# Sheet8.net
KiCad netlist of a schematic drawn in Altium Designer
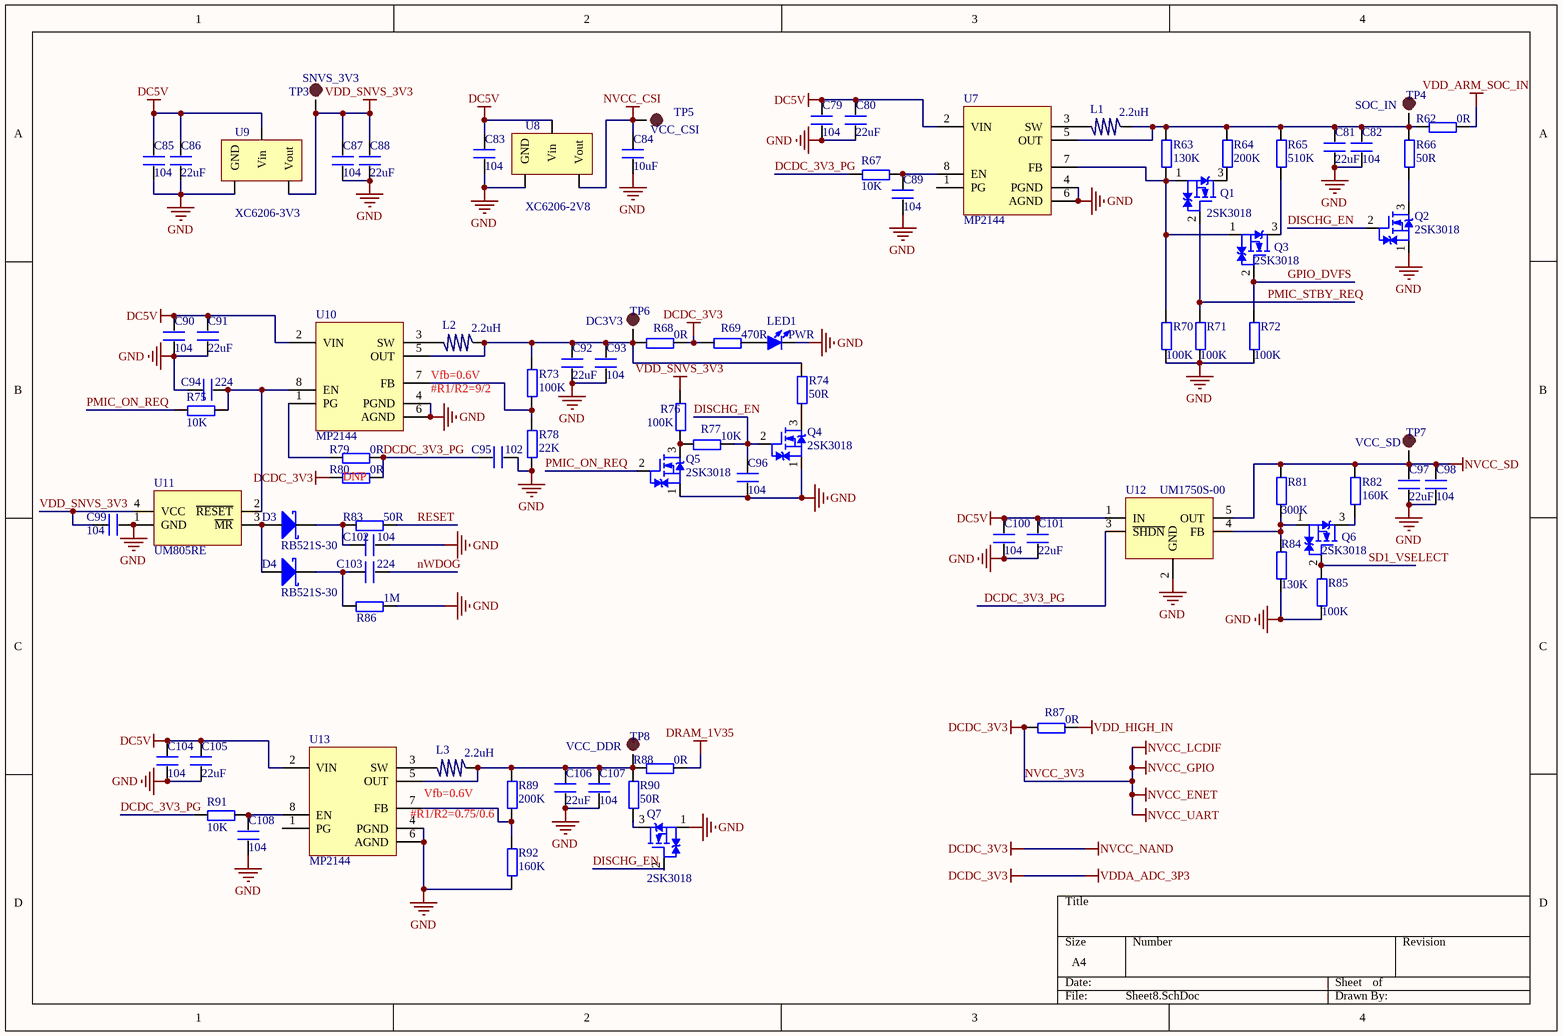
[diagram p0: Sheet8.SchDoc]

(export (version "E")
  (design (tool "Eeschema 10.0.6"))
  (components
    (comp (ref "C79")
      (value "104")
      (footprint "C 0402")
      (libsource (lib "IMX6ULL_CORE(核心板)_V1.4") (part "C"))
    )
    (comp (ref "C80")
      (value "22uF")
      (footprint "C 0402")
      (libsource (lib "IMX6ULL_CORE(核心板)_V1.4") (part "C"))
    )
    (comp (ref "C81")
      (value "22uF")
      (footprint "C 0402")
      (libsource (lib "IMX6ULL_CORE(核心板)_V1.4") (part "C"))
    )
    (comp (ref "C82")
      (value "104")
      (footprint "C 0402")
      (libsource (lib "IMX6ULL_CORE(核心板)_V1.4") (part "C"))
    )
    (comp (ref "C83")
      (value "104")
      (footprint "C 0402")
      (libsource (lib "IMX6ULL_CORE(核心板)_V1.4") (part "C"))
    )
    (comp (ref "C84")
      (value "10uF")
      (footprint "C 0402")
      (libsource (lib "IMX6ULL_CORE(核心板)_V1.4") (part "C"))
    )
    (comp (ref "C85")
      (value "104")
      (footprint "C 0402")
      (libsource (lib "IMX6ULL_CORE(核心板)_V1.4") (part "C"))
    )
    (comp (ref "C86")
      (value "22uF")
      (footprint "C 0402")
      (libsource (lib "IMX6ULL_CORE(核心板)_V1.4") (part "C"))
    )
    (comp (ref "C87")
      (value "104")
      (footprint "C 0402")
      (libsource (lib "IMX6ULL_CORE(核心板)_V1.4") (part "C"))
    )
    (comp (ref "C88")
      (value "22uF")
      (footprint "C 0402")
      (libsource (lib "IMX6ULL_CORE(核心板)_V1.4") (part "C"))
    )
    (comp (ref "C89")
      (value "104")
      (footprint "C 0402")
      (libsource (lib "IMX6ULL_CORE(核心板)_V1.4") (part "C"))
    )
    (comp (ref "C90")
      (value "104")
      (footprint "C 0402")
      (libsource (lib "IMX6ULL_CORE(核心板)_V1.4") (part "C"))
    )
    (comp (ref "C91")
      (value "22uF")
      (footprint "C 0402")
      (libsource (lib "IMX6ULL_CORE(核心板)_V1.4") (part "C"))
    )
    (comp (ref "C92")
      (value "22uF")
      (footprint "C 0402")
      (libsource (lib "IMX6ULL_CORE(核心板)_V1.4") (part "C"))
    )
    (comp (ref "C93")
      (value "104")
      (footprint "C 0402")
      (libsource (lib "IMX6ULL_CORE(核心板)_V1.4") (part "C"))
    )
    (comp (ref "C94")
      (value "224")
      (footprint "C 0402")
      (libsource (lib "IMX6ULL_CORE(核心板)_V1.4") (part "C"))
    )
    (comp (ref "C95")
      (value "102")
      (footprint "C 0402")
      (libsource (lib "IMX6ULL_CORE(核心板)_V1.4") (part "C"))
    )
    (comp (ref "C96")
      (value "104")
      (footprint "C 0402")
      (libsource (lib "IMX6ULL_CORE(核心板)_V1.4") (part "C"))
    )
    (comp (ref "C97")
      (value "22uF")
      (footprint "C 0402")
      (libsource (lib "IMX6ULL_CORE(核心板)_V1.4") (part "C"))
    )
    (comp (ref "C98")
      (value "104")
      (footprint "C 0402")
      (libsource (lib "IMX6ULL_CORE(核心板)_V1.4") (part "C"))
    )
    (comp (ref "C99")
      (value "104")
      (footprint "C 0402")
      (libsource (lib "IMX6ULL_CORE(核心板)_V1.4") (part "C"))
    )
    (comp (ref "C100")
      (value "104")
      (footprint "C 0402")
      (libsource (lib "IMX6ULL_CORE(核心板)_V1.4") (part "C"))
    )
    (comp (ref "C101")
      (value "22uF")
      (footprint "C 0402")
      (libsource (lib "IMX6ULL_CORE(核心板)_V1.4") (part "C"))
    )
    (comp (ref "C102")
      (value "104")
      (footprint "C 0402")
      (libsource (lib "IMX6ULL_CORE(核心板)_V1.4") (part "C"))
    )
    (comp (ref "C103")
      (value "224")
      (footprint "C 0402")
      (libsource (lib "IMX6ULL_CORE(核心板)_V1.4") (part "C"))
    )
    (comp (ref "C104")
      (value "104")
      (footprint "C 0402")
      (libsource (lib "IMX6ULL_CORE(核心板)_V1.4") (part "C"))
    )
    (comp (ref "C105")
      (value "22uF")
      (footprint "C 0402")
      (libsource (lib "IMX6ULL_CORE(核心板)_V1.4") (part "C"))
    )
    (comp (ref "C106")
      (value "22uF")
      (footprint "C 0402")
      (libsource (lib "IMX6ULL_CORE(核心板)_V1.4") (part "C"))
    )
    (comp (ref "C107")
      (value "104")
      (footprint "C 0402")
      (libsource (lib "IMX6ULL_CORE(核心板)_V1.4") (part "C"))
    )
    (comp (ref "C108")
      (value "104")
      (footprint "C 0402")
      (libsource (lib "IMX6ULL_CORE(核心板)_V1.4") (part "C"))
    )
    (comp (ref "D3")
      (value "RB521S-30")
      (footprint "SOD-523")
      (libsource (lib "IMX6ULL_CORE(核心板)_V1.4") (part "RB521S-30"))
    )
    (comp (ref "D4")
      (value "RB521S-30")
      (footprint "SOD-523")
      (libsource (lib "IMX6ULL_CORE(核心板)_V1.4") (part "RB521S-30"))
    )
    (comp (ref "L1")
      (value "2.2uH")
      (footprint "NR3015")
      (libsource (lib "IMX6ULL_CORE(核心板)_V1.4") (part "L"))
    )
    (comp (ref "L2")
      (value "2.2uH")
      (footprint "NR3015")
      (libsource (lib "IMX6ULL_CORE(核心板)_V1.4") (part "L"))
    )
    (comp (ref "L3")
      (value "2.2uH")
      (footprint "NR3015")
      (libsource (lib "IMX6ULL_CORE(核心板)_V1.4") (part "L"))
    )
    (comp (ref "LED1")
      (value "PWR")
      (footprint "LED 0603B")
      (description "贴片LED")
      (fields (field (name "版权归属") "源创客"))
      (libsource (lib "IMX6ULL_CORE(核心板)_V1.4") (part "LED-SMD"))
    )
    (comp (ref "Q1")
      (value "2SK3018")
      (footprint "SC70-3L")
      (description "N沟场效应管  30V,0.1A")
      (fields (field (name "版权归属") "源创客"))
      (libsource (lib "IMX6ULL_CORE(核心板)_V1.4") (part "2SK3018"))
    )
    (comp (ref "Q2")
      (value "2SK3018")
      (footprint "SC70-3L")
      (description "N沟场效应管  30V,0.1A")
      (fields (field (name "版权归属") "源创客"))
      (libsource (lib "IMX6ULL_CORE(核心板)_V1.4") (part "2SK3018"))
    )
    (comp (ref "Q3")
      (value "2SK3018")
      (footprint "SC70-3L")
      (description "N沟场效应管  30V,0.1A")
      (fields (field (name "版权归属") "源创客"))
      (libsource (lib "IMX6ULL_CORE(核心板)_V1.4") (part "2SK3018"))
    )
    (comp (ref "Q4")
      (value "2SK3018")
      (footprint "SC70-3L")
      (description "N沟场效应管  30V,0.1A")
      (fields (field (name "版权归属") "源创客"))
      (libsource (lib "IMX6ULL_CORE(核心板)_V1.4") (part "2SK3018"))
    )
    (comp (ref "Q5")
      (value "2SK3018")
      (footprint "SC70-3L")
      (description "N沟场效应管  30V,0.1A")
      (fields (field (name "版权归属") "源创客"))
      (libsource (lib "IMX6ULL_CORE(核心板)_V1.4") (part "2SK3018"))
    )
    (comp (ref "Q6")
      (value "2SK3018")
      (footprint "SC70-3L")
      (description "N沟场效应管  30V,0.1A")
      (fields (field (name "版权归属") "源创客"))
      (libsource (lib "IMX6ULL_CORE(核心板)_V1.4") (part "2SK3018"))
    )
    (comp (ref "Q7")
      (value "2SK3018")
      (footprint "SC70-3L")
      (description "N沟场效应管  30V,0.1A")
      (fields (field (name "版权归属") "源创客"))
      (libsource (lib "IMX6ULL_CORE(核心板)_V1.4") (part "2SK3018"))
    )
    (comp (ref "R62") (value "0R") (footprint "R 0402") (libsource (lib "IMX6ULL_CORE(核心板)_V1.4") (part "R")))
    (comp (ref "R63")
      (value "130K")
      (footprint "R 0402")
      (libsource (lib "IMX6ULL_CORE(核心板)_V1.4") (part "R"))
    )
    (comp (ref "R64")
      (value "200K")
      (footprint "R 0402")
      (libsource (lib "IMX6ULL_CORE(核心板)_V1.4") (part "R"))
    )
    (comp (ref "R65")
      (value "510K")
      (footprint "R 0402")
      (libsource (lib "IMX6ULL_CORE(核心板)_V1.4") (part "R"))
    )
    (comp (ref "R66")
      (value "50R")
      (footprint "R 0402")
      (libsource (lib "IMX6ULL_CORE(核心板)_V1.4") (part "R"))
    )
    (comp (ref "R67")
      (value "10K")
      (footprint "R 0402")
      (libsource (lib "IMX6ULL_CORE(核心板)_V1.4") (part "R"))
    )
    (comp (ref "R68") (value "0R") (footprint "R 0402") (libsource (lib "IMX6ULL_CORE(核心板)_V1.4") (part "R")))
    (comp (ref "R69")
      (value "470R")
      (footprint "R 0402")
      (libsource (lib "IMX6ULL_CORE(核心板)_V1.4") (part "R"))
    )
    (comp (ref "R70")
      (value "100K")
      (footprint "R 0402")
      (libsource (lib "IMX6ULL_CORE(核心板)_V1.4") (part "R"))
    )
    (comp (ref "R71")
      (value "100K")
      (footprint "R 0402")
      (libsource (lib "IMX6ULL_CORE(核心板)_V1.4") (part "R"))
    )
    (comp (ref "R72")
      (value "100K")
      (footprint "R 0402")
      (libsource (lib "IMX6ULL_CORE(核心板)_V1.4") (part "R"))
    )
    (comp (ref "R73")
      (value "100K")
      (footprint "R 0402")
      (libsource (lib "IMX6ULL_CORE(核心板)_V1.4") (part "R"))
    )
    (comp (ref "R74")
      (value "50R")
      (footprint "R 0402")
      (libsource (lib "IMX6ULL_CORE(核心板)_V1.4") (part "R"))
    )
    (comp (ref "R75")
      (value "10K")
      (footprint "R 0402")
      (libsource (lib "IMX6ULL_CORE(核心板)_V1.4") (part "R"))
    )
    (comp (ref "R76")
      (value "100K")
      (footprint "R 0402")
      (libsource (lib "IMX6ULL_CORE(核心板)_V1.4") (part "R"))
    )
    (comp (ref "R77")
      (value "10K")
      (footprint "R 0402")
      (libsource (lib "IMX6ULL_CORE(核心板)_V1.4") (part "R"))
    )
    (comp (ref "R78")
      (value "22K")
      (footprint "R 0402")
      (libsource (lib "IMX6ULL_CORE(核心板)_V1.4") (part "R"))
    )
    (comp (ref "R79") (value "0R") (footprint "R 0402") (libsource (lib "IMX6ULL_CORE(核心板)_V1.4") (part "R")))
    (comp (ref "R80") (value "0R") (footprint "R 0402") (libsource (lib "IMX6ULL_CORE(核心板)_V1.4") (part "R")))
    (comp (ref "R81")
      (value "300K")
      (footprint "R 0402")
      (libsource (lib "IMX6ULL_CORE(核心板)_V1.4") (part "R"))
    )
    (comp (ref "R82")
      (value "160K")
      (footprint "R 0402")
      (libsource (lib "IMX6ULL_CORE(核心板)_V1.4") (part "R"))
    )
    (comp (ref "R83")
      (value "50R")
      (footprint "R 0402")
      (libsource (lib "IMX6ULL_CORE(核心板)_V1.4") (part "R"))
    )
    (comp (ref "R84")
      (value "130K")
      (footprint "R 0402")
      (libsource (lib "IMX6ULL_CORE(核心板)_V1.4") (part "R"))
    )
    (comp (ref "R85")
      (value "100K")
      (footprint "R 0402")
      (libsource (lib "IMX6ULL_CORE(核心板)_V1.4") (part "R"))
    )
    (comp (ref "R86") (value "1M") (footprint "R 0402") (libsource (lib "IMX6ULL_CORE(核心板)_V1.4") (part "R")))
    (comp (ref "R87") (value "0R") (footprint "R 0402") (libsource (lib "IMX6ULL_CORE(核心板)_V1.4") (part "R")))
    (comp (ref "R88") (value "0R") (footprint "R 0402") (libsource (lib "IMX6ULL_CORE(核心板)_V1.4") (part "R")))
    (comp (ref "R89")
      (value "200K")
      (footprint "R 0402")
      (libsource (lib "IMX6ULL_CORE(核心板)_V1.4") (part "R"))
    )
    (comp (ref "R90")
      (value "50R")
      (footprint "R 0402")
      (libsource (lib "IMX6ULL_CORE(核心板)_V1.4") (part "R"))
    )
    (comp (ref "R91")
      (value "10K")
      (footprint "R 0402")
      (libsource (lib "IMX6ULL_CORE(核心板)_V1.4") (part "R"))
    )
    (comp (ref "R92")
      (value "160K")
      (footprint "R 0402")
      (libsource (lib "IMX6ULL_CORE(核心板)_V1.4") (part "R"))
    )
    (comp (ref "TP3")
      (value "SNVS_3V3")
      (footprint "TP-1.0")
      (description "测试点")
      (libsource (lib "IMX6ULL_CORE(核心板)_V1.4") (part "TEST-POINT"))
    )
    (comp (ref "TP4")
      (value "SOC_IN")
      (footprint "TP-1.0")
      (description "测试点")
      (libsource (lib "IMX6ULL_CORE(核心板)_V1.4") (part "TEST-POINT"))
    )
    (comp (ref "TP5")
      (value "VCC_CSI")
      (footprint "TP-1.0")
      (description "测试点")
      (libsource (lib "IMX6ULL_CORE(核心板)_V1.4") (part "TEST-POINT"))
    )
    (comp (ref "TP6")
      (value "DC3V3")
      (footprint "TP-1.0")
      (description "测试点")
      (libsource (lib "IMX6ULL_CORE(核心板)_V1.4") (part "TEST-POINT"))
    )
    (comp (ref "TP7")
      (value "VCC_SD")
      (footprint "TP-1.0")
      (description "测试点")
      (libsource (lib "IMX6ULL_CORE(核心板)_V1.4") (part "TEST-POINT"))
    )
    (comp (ref "TP8")
      (value "VCC_DDR")
      (footprint "TP-1.0")
      (description "测试点")
      (libsource (lib "IMX6ULL_CORE(核心板)_V1.4") (part "TEST-POINT"))
    )
    (comp (ref "U7")
      (value "MP2144")
      (footprint "SOT23-8L")
      (libsource (lib "IMX6ULL_CORE(核心板)_V1.4") (part "MP2144"))
    )
    (comp (ref "U8")
      (value "XC6206-2V8")
      (footprint "SOT23-3L")
      (libsource (lib "Schlib1") (part "XC6206-3V3"))
    )
    (comp (ref "U9")
      (value "XC6206-3V3")
      (footprint "SOT23-3L")
      (libsource (lib "Schlib1") (part "XC6206-3V3"))
    )
    (comp (ref "U10")
      (value "MP2144")
      (footprint "SOT23-8L")
      (libsource (lib "IMX6ULL_CORE(核心板)_V1.4") (part "MP2144"))
    )
    (comp (ref "U11")
      (value "UM805RE")
      (footprint "SOT143")
      (libsource (lib "IMX6ULL_CORE(核心板)_V1.4") (part "UM805RE"))
    )
    (comp (ref "U12")
      (value "UM1750S-00")
      (footprint "SOT23-5L")
      (libsource (lib "IMX6ULL_CORE(核心板)_V1.4") (part "UM1750S-00"))
    )
    (comp (ref "U13")
      (value "MP2144")
      (footprint "SOT23-8L")
      (libsource (lib "IMX6ULL_CORE(核心板)_V1.4") (part "MP2144"))
    )
  )
  (nets
    (net (code "1") (name "/DCDC_3V3_PG") (class "Default")
      (node (ref "C95") (pin "2") (pintype "passive"))
      (node (ref "R67") (pin "1") (pintype "passive"))
      (node (ref "R79") (pin "2") (pintype "passive"))
      (node (ref "R80") (pin "2") (pintype "passive"))
      (node (ref "R91") (pin "1") (pintype "passive"))
      (node (ref "U12") (pin "3") (pinfunction "~{SHDN}_3") (pintype "passive"))
    )
    (net (code "2") (name "/DISCHG_EN") (class "Default")
      (node (ref "C96") (pin "1") (pintype "passive"))
      (node (ref "Q2") (pin "2") (pinfunction "G_2") (pintype "passive"))
      (node (ref "Q4") (pin "2") (pinfunction "G_2") (pintype "passive"))
      (node (ref "Q7") (pin "2") (pinfunction "G_2") (pintype "passive"))
      (node (ref "R77") (pin "2") (pintype "passive"))
    )
    (net (code "3") (name "/GPIO_DVFS") (class "Default")
      (node (ref "Q3") (pin "2") (pinfunction "G_2") (pintype "passive"))
      (node (ref "R72") (pin "2") (pintype "passive"))
    )
    (net (code "4") (name "/PMIC_ON_REQ") (class "Default")
      (node (ref "Q5") (pin "2") (pinfunction "G_2") (pintype "passive"))
      (node (ref "R75") (pin "1") (pintype "passive"))
    )
    (net (code "5") (name "/PMIC_STBY_REQ") (class "Default")
      (node (ref "Q1") (pin "2") (pinfunction "G_2") (pintype "passive"))
      (node (ref "R71") (pin "2") (pintype "passive"))
    )
    (net (code "6") (name "/RESET") (class "Default") (node (ref "R83") (pin "2") (pintype "passive")))
    (net (code "7") (name "/SD1_VSELECT") (class "Default")
      (node (ref "Q6") (pin "2") (pinfunction "G_2") (pintype "passive"))
      (node (ref "R85") (pin "2") (pintype "passive"))
    )
    (net (code "8") (name "/nWDOG") (class "Default") (node (ref "C103") (pin "1") (pintype "passive")))
    (net (code "9") (name "DC5V") (class "Default")
      (node (ref "C100") (pin "2") (pintype "passive"))
      (node (ref "C101") (pin "2") (pintype "passive"))
      (node (ref "C104") (pin "2") (pintype "passive"))
      (node (ref "C105") (pin "2") (pintype "passive"))
      (node (ref "C79") (pin "2") (pintype "passive"))
      (node (ref "C80") (pin "2") (pintype "passive"))
      (node (ref "C83") (pin "2") (pintype "passive"))
      (node (ref "C85") (pin "2") (pintype "passive"))
      (node (ref "C86") (pin "2") (pintype "passive"))
      (node (ref "C90") (pin "2") (pintype "passive"))
      (node (ref "C91") (pin "2") (pintype "passive"))
      (node (ref "U10") (pin "2") (pinfunction "VIN_2") (pintype "passive"))
      (node (ref "U12") (pin "1") (pinfunction "IN_1") (pintype "passive"))
      (node (ref "U13") (pin "2") (pinfunction "VIN_2") (pintype "passive"))
      (node (ref "U7") (pin "2") (pinfunction "VIN_2") (pintype "passive"))
      (node (ref "U8") (pin "2") (pinfunction "Vin_2") (pintype "passive"))
      (node (ref "U9") (pin "2") (pinfunction "Vin_2") (pintype "passive"))
    )
    (net (code "10") (name "DCDC_3V3") (class "Default")
      (node (ref "R68") (pin "2") (pintype "passive"))
      (node (ref "R69") (pin "1") (pintype "passive"))
      (node (ref "R80") (pin "1") (pintype "passive"))
      (node (ref "R87") (pin "1") (pintype "passive"))
    )
    (net (code "11") (name "DRAM_1V35") (class "Default") (node (ref "R88") (pin "2") (pintype "passive")))
    (net (code "12") (name "GND") (class "Default")
      (node (ref "C100") (pin "1") (pintype "passive"))
      (node (ref "C101") (pin "1") (pintype "passive"))
      (node (ref "C102") (pin "1") (pintype "passive"))
      (node (ref "C104") (pin "1") (pintype "passive"))
      (node (ref "C105") (pin "1") (pintype "passive"))
      (node (ref "C106") (pin "2") (pintype "passive"))
      (node (ref "C107") (pin "2") (pintype "passive"))
      (node (ref "C108") (pin "1") (pintype "passive"))
      (node (ref "C79") (pin "1") (pintype "passive"))
      (node (ref "C80") (pin "1") (pintype "passive"))
      (node (ref "C81") (pin "1") (pintype "passive"))
      (node (ref "C82") (pin "1") (pintype "passive"))
      (node (ref "C83") (pin "1") (pintype "passive"))
      (node (ref "C84") (pin "1") (pintype "passive"))
      (node (ref "C85") (pin "1") (pintype "passive"))
      (node (ref "C86") (pin "1") (pintype "passive"))
      (node (ref "C87") (pin "1") (pintype "passive"))
      (node (ref "C88") (pin "1") (pintype "passive"))
      (node (ref "C89") (pin "1") (pintype "passive"))
      (node (ref "C90") (pin "1") (pintype "passive"))
      (node (ref "C91") (pin "1") (pintype "passive"))
      (node (ref "C92") (pin "2") (pintype "passive"))
      (node (ref "C93") (pin "2") (pintype "passive"))
      (node (ref "C94") (pin "2") (pintype "passive"))
      (node (ref "C95") (pin "1") (pintype "passive"))
      (node (ref "C96") (pin "2") (pintype "passive"))
      (node (ref "C97") (pin "1") (pintype "passive"))
      (node (ref "C98") (pin "1") (pintype "passive"))
      (node (ref "C99") (pin "1") (pintype "passive"))
      (node (ref "LED1") (pin "2") (pinfunction "K_2") (pintype "passive"))
      (node (ref "Q2") (pin "1") (pinfunction "S_1") (pintype "passive"))
      (node (ref "Q4") (pin "1") (pinfunction "S_1") (pintype "passive"))
      (node (ref "Q5") (pin "1") (pinfunction "S_1") (pintype "passive"))
      (node (ref "Q7") (pin "1") (pinfunction "S_1") (pintype "passive"))
      (node (ref "R70") (pin "1") (pintype "passive"))
      (node (ref "R71") (pin "1") (pintype "passive"))
      (node (ref "R72") (pin "1") (pintype "passive"))
      (node (ref "R78") (pin "1") (pintype "passive"))
      (node (ref "R84") (pin "1") (pintype "passive"))
      (node (ref "R85") (pin "1") (pintype "passive"))
      (node (ref "R86") (pin "2") (pintype "passive"))
      (node (ref "R92") (pin "1") (pintype "passive"))
      (node (ref "U10") (pin "4") (pinfunction "PGND_4") (pintype "passive"))
      (node (ref "U10") (pin "6") (pinfunction "AGND_6") (pintype "passive"))
      (node (ref "U11") (pin "1") (pinfunction "GND_1") (pintype "passive"))
      (node (ref "U12") (pin "2") (pinfunction "GND_2") (pintype "passive"))
      (node (ref "U13") (pin "4") (pinfunction "PGND_4") (pintype "passive"))
      (node (ref "U13") (pin "6") (pinfunction "AGND_6") (pintype "passive"))
      (node (ref "U7") (pin "4") (pinfunction "PGND_4") (pintype "passive"))
      (node (ref "U7") (pin "6") (pinfunction "AGND_6") (pintype "passive"))
      (node (ref "U8") (pin "0") (pinfunction "GND_0") (pintype "passive"))
      (node (ref "U9") (pin "0") (pinfunction "GND_0") (pintype "passive"))
    )
    (net (code "13") (name "NVCC_CSI") (class "Default")
      (node (ref "C84") (pin "2") (pintype "passive"))
      (node (ref "TP5") (pin "1") (pinfunction "1_1") (pintype "passive"))
      (node (ref "U8") (pin "1") (pinfunction "Vout_1") (pintype "passive"))
    )
    (net (code "14") (name "NVCC_SD") (class "Default")
      (node (ref "C97") (pin "2") (pintype "passive"))
      (node (ref "C98") (pin "2") (pintype "passive"))
      (node (ref "R81") (pin "2") (pintype "passive"))
      (node (ref "R82") (pin "2") (pintype "passive"))
      (node (ref "TP7") (pin "1") (pinfunction "1_1") (pintype "passive"))
      (node (ref "U12") (pin "5") (pinfunction "OUT_5") (pintype "passive"))
    )
    (net (code "15") (name "Net-(D3-A)") (class "Default")
      (node (ref "D3") (pin "1") (pinfunction "A_1") (pintype "passive"))
      (node (ref "D4") (pin "1") (pinfunction "A_1") (pintype "passive"))
      (node (ref "U11") (pin "3") (pinfunction "~{MR}_3") (pintype "passive"))
    )
    (net (code "16") (name "Net-(D3-C)") (class "Default")
      (node (ref "C102") (pin "2") (pintype "passive"))
      (node (ref "D3") (pin "2") (pinfunction "C_2") (pintype "passive"))
      (node (ref "R83") (pin "1") (pintype "passive"))
    )
    (net (code "17") (name "Net-(D4-C)") (class "Default")
      (node (ref "C103") (pin "2") (pintype "passive"))
      (node (ref "D4") (pin "2") (pinfunction "C_2") (pintype "passive"))
      (node (ref "R86") (pin "1") (pintype "passive"))
    )
    (net (code "18") (name "Net-(LED1-A)") (class "Default")
      (node (ref "LED1") (pin "1") (pinfunction "A_1") (pintype "passive"))
      (node (ref "R69") (pin "2") (pintype "passive"))
    )
    (net (code "19") (name "Net-(Q1-D)") (class "Default")
      (node (ref "Q1") (pin "3") (pinfunction "D_3") (pintype "passive"))
      (node (ref "R64") (pin "1") (pintype "passive"))
    )
    (net (code "20") (name "Net-(Q1-S)") (class "Default")
      (node (ref "Q1") (pin "1") (pinfunction "S_1") (pintype "passive"))
      (node (ref "Q3") (pin "1") (pinfunction "S_1") (pintype "passive"))
      (node (ref "R63") (pin "1") (pintype "passive"))
      (node (ref "R70") (pin "2") (pintype "passive"))
      (node (ref "U7") (pin "7") (pinfunction "FB_7") (pintype "passive"))
    )
    (net (code "21") (name "Net-(Q2-D)") (class "Default")
      (node (ref "Q2") (pin "3") (pinfunction "D_3") (pintype "passive"))
      (node (ref "R66") (pin "1") (pintype "passive"))
    )
    (net (code "22") (name "Net-(Q3-D)") (class "Default")
      (node (ref "Q3") (pin "3") (pinfunction "D_3") (pintype "passive"))
      (node (ref "R65") (pin "1") (pintype "passive"))
    )
    (net (code "23") (name "Net-(Q4-D)") (class "Default")
      (node (ref "Q4") (pin "3") (pinfunction "D_3") (pintype "passive"))
      (node (ref "R74") (pin "1") (pintype "passive"))
    )
    (net (code "24") (name "Net-(Q5-D)") (class "Default")
      (node (ref "Q5") (pin "3") (pinfunction "D_3") (pintype "passive"))
      (node (ref "R76") (pin "1") (pintype "passive"))
      (node (ref "R77") (pin "1") (pintype "passive"))
    )
    (net (code "25") (name "Net-(Q6-D)") (class "Default")
      (node (ref "Q6") (pin "3") (pinfunction "D_3") (pintype "passive"))
      (node (ref "R82") (pin "1") (pintype "passive"))
    )
    (net (code "26") (name "Net-(Q6-S)") (class "Default")
      (node (ref "Q6") (pin "1") (pinfunction "S_1") (pintype "passive"))
      (node (ref "R81") (pin "1") (pintype "passive"))
      (node (ref "R84") (pin "2") (pintype "passive"))
      (node (ref "U12") (pin "4") (pinfunction "FB_4") (pintype "passive"))
    )
    (net (code "27") (name "Net-(Q7-D)") (class "Default")
      (node (ref "Q7") (pin "3") (pinfunction "D_3") (pintype "passive"))
      (node (ref "R90") (pin "1") (pintype "passive"))
    )
    (net (code "28") (name "Net-(U7-EN)") (class "Default")
      (node (ref "C89") (pin "2") (pintype "passive"))
      (node (ref "R67") (pin "2") (pintype "passive"))
      (node (ref "U7") (pin "8") (pinfunction "EN_8") (pintype "passive"))
    )
    (net (code "29") (name "Net-(U7-OUT)") (class "Default")
      (node (ref "C81") (pin "2") (pintype "passive"))
      (node (ref "C82") (pin "2") (pintype "passive"))
      (node (ref "L1") (pin "1") (pintype "passive"))
      (node (ref "R62") (pin "1") (pintype "passive"))
      (node (ref "R63") (pin "2") (pintype "passive"))
      (node (ref "R64") (pin "2") (pintype "passive"))
      (node (ref "R65") (pin "2") (pintype "passive"))
      (node (ref "R66") (pin "2") (pintype "passive"))
      (node (ref "TP4") (pin "1") (pinfunction "1_1") (pintype "passive"))
      (node (ref "U7") (pin "5") (pinfunction "OUT_5") (pintype "passive"))
    )
    (net (code "30") (name "Net-(U7-SW)") (class "Default")
      (node (ref "L1") (pin "2") (pintype "passive"))
      (node (ref "U7") (pin "3") (pinfunction "SW_3") (pintype "passive"))
    )
    (net (code "31") (name "Net-(U10-EN)") (class "Default")
      (node (ref "C94") (pin "1") (pintype "passive"))
      (node (ref "R75") (pin "2") (pintype "passive"))
      (node (ref "U10") (pin "8") (pinfunction "EN_8") (pintype "passive"))
      (node (ref "U11") (pin "2") (pinfunction "~{RESET}_2") (pintype "passive"))
    )
    (net (code "32") (name "Net-(U10-FB)") (class "Default")
      (node (ref "R73") (pin "1") (pintype "passive"))
      (node (ref "R78") (pin "2") (pintype "passive"))
      (node (ref "U10") (pin "7") (pinfunction "FB_7") (pintype "passive"))
    )
    (net (code "33") (name "Net-(U10-OUT)") (class "Default")
      (node (ref "C92") (pin "1") (pintype "passive"))
      (node (ref "C93") (pin "1") (pintype "passive"))
      (node (ref "L2") (pin "1") (pintype "passive"))
      (node (ref "R68") (pin "1") (pintype "passive"))
      (node (ref "R73") (pin "2") (pintype "passive"))
      (node (ref "R74") (pin "2") (pintype "passive"))
      (node (ref "TP6") (pin "1") (pinfunction "1_1") (pintype "passive"))
      (node (ref "U10") (pin "5") (pinfunction "OUT_5") (pintype "passive"))
    )
    (net (code "34") (name "Net-(U10-PG)") (class "Default")
      (node (ref "R79") (pin "1") (pintype "passive"))
      (node (ref "U10") (pin "1") (pinfunction "PG_1") (pintype "passive"))
    )
    (net (code "35") (name "Net-(U10-SW)") (class "Default")
      (node (ref "L2") (pin "2") (pintype "passive"))
      (node (ref "U10") (pin "3") (pinfunction "SW_3") (pintype "passive"))
    )
    (net (code "36") (name "Net-(U13-EN)") (class "Default")
      (node (ref "C108") (pin "2") (pintype "passive"))
      (node (ref "R91") (pin "2") (pintype "passive"))
      (node (ref "U13") (pin "8") (pinfunction "EN_8") (pintype "passive"))
    )
    (net (code "37") (name "Net-(U13-FB)") (class "Default")
      (node (ref "R89") (pin "1") (pintype "passive"))
      (node (ref "R92") (pin "2") (pintype "passive"))
      (node (ref "U13") (pin "7") (pinfunction "FB_7") (pintype "passive"))
    )
    (net (code "38") (name "Net-(U13-OUT)") (class "Default")
      (node (ref "C106") (pin "1") (pintype "passive"))
      (node (ref "C107") (pin "1") (pintype "passive"))
      (node (ref "L3") (pin "1") (pintype "passive"))
      (node (ref "R88") (pin "1") (pintype "passive"))
      (node (ref "R89") (pin "2") (pintype "passive"))
      (node (ref "R90") (pin "2") (pintype "passive"))
      (node (ref "TP8") (pin "1") (pinfunction "1_1") (pintype "passive"))
      (node (ref "U13") (pin "5") (pinfunction "OUT_5") (pintype "passive"))
    )
    (net (code "39") (name "Net-(U13-SW)") (class "Default")
      (node (ref "L3") (pin "2") (pintype "passive"))
      (node (ref "U13") (pin "3") (pinfunction "SW_3") (pintype "passive"))
    )
    (net (code "40") (name "VDD_ARM_SOC_IN") (class "Default")
      (node (ref "R62") (pin "2") (pintype "passive"))
    )
    (net (code "41") (name "VDD_HIGH_IN") (class "Default") (node (ref "R87") (pin "2") (pintype "passive")))
    (net (code "42") (name "VDD_SNVS_3V3") (class "Default")
      (node (ref "C87") (pin "2") (pintype "passive"))
      (node (ref "C88") (pin "2") (pintype "passive"))
      (node (ref "C99") (pin "2") (pintype "passive"))
      (node (ref "R76") (pin "2") (pintype "passive"))
      (node (ref "TP3") (pin "1") (pinfunction "1_1") (pintype "passive"))
      (node (ref "U11") (pin "4") (pinfunction "VCC_4") (pintype "passive"))
      (node (ref "U9") (pin "1") (pinfunction "Vout_1") (pintype "passive"))
    )
    (net (code "43") (name "unconnected-(U7-PG-Pad1)") (class "Default")
      (node (ref "U7") (pin "1") (pinfunction "PG_1") (pintype "passive"))
    )
    (net (code "44") (name "unconnected-(U13-PG-Pad1)") (class "Default")
      (node (ref "U13") (pin "1") (pinfunction "PG_1") (pintype "passive"))
    )
  )
)
